# as5147_breakout.net
KiCad netlist of a schematic drawn in EAGLE
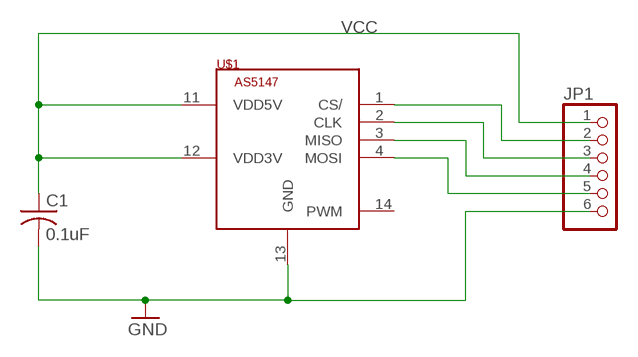
[diagram p0: schematic, sheet 1]

(export (version "E")
  (design (tool "Eeschema 10.0.6"))
  (components
    (comp (ref "C1")
      (value "0.1uF")
      (footprint "eagle-import:C0603")
      (libsource (lib "eagle-import") (part "C-USC0603"))
    )
    (comp (ref "JP1")
      (value "PINHD-1X6")
      (footprint "eagle-import:1X06")
      (libsource (lib "eagle-import") (part "PINHD-1X6"))
    )
    (comp (ref "U$1")
      (value "AS5147")
      (footprint "eagle-import:TSSOP14")
      (libsource (lib "eagle-import") (part "AS5147"))
    )
  )
  (nets
    (net (code "1") (name "/VCC") (class "Default")
      (node (ref "C1") (pin "1") (pinfunction "1_1") (pintype "passive"))
      (node (ref "JP1") (pin "1") (pinfunction "1_1") (pintype "passive"))
      (node (ref "U$1") (pin "11") (pinfunction "VDD5V_11") (pintype "bidirectional"))
      (node (ref "U$1") (pin "12") (pinfunction "VDD3V_12") (pintype "bidirectional"))
    )
    (net (code "2") (name "GND") (class "Default")
      (node (ref "C1") (pin "2") (pinfunction "2_2") (pintype "passive"))
      (node (ref "JP1") (pin "6") (pinfunction "6_6") (pintype "passive"))
      (node (ref "U$1") (pin "13") (pinfunction "GND_13") (pintype "bidirectional"))
    )
    (net (code "3") (name "Net-(U$1-CLK)") (class "Default")
      (node (ref "JP1") (pin "3") (pinfunction "3_3") (pintype "passive"))
      (node (ref "U$1") (pin "2") (pinfunction "CLK_2") (pintype "bidirectional"))
    )
    (net (code "4") (name "Net-(U$1-CS{slash})") (class "Default")
      (node (ref "JP1") (pin "2") (pinfunction "2_2") (pintype "passive"))
      (node (ref "U$1") (pin "1") (pinfunction "CS/_1") (pintype "bidirectional"))
    )
    (net (code "5") (name "Net-(U$1-MISO)") (class "Default")
      (node (ref "JP1") (pin "4") (pinfunction "4_4") (pintype "passive"))
      (node (ref "U$1") (pin "3") (pinfunction "MISO_3") (pintype "bidirectional"))
    )
    (net (code "6") (name "Net-(U$1-MOSI)") (class "Default")
      (node (ref "JP1") (pin "5") (pinfunction "5_5") (pintype "passive"))
      (node (ref "U$1") (pin "4") (pinfunction "MOSI_4") (pintype "bidirectional"))
    )
    (net (code "7") (name "unconnected-(U$1-PWM-Pad14)") (class "Default")
      (node (ref "U$1") (pin "14") (pinfunction "PWM_14") (pintype "bidirectional"))
    )
  )
)
